# pandora_A_v1.net
KiCad netlist of a schematic drawn in EAGLE
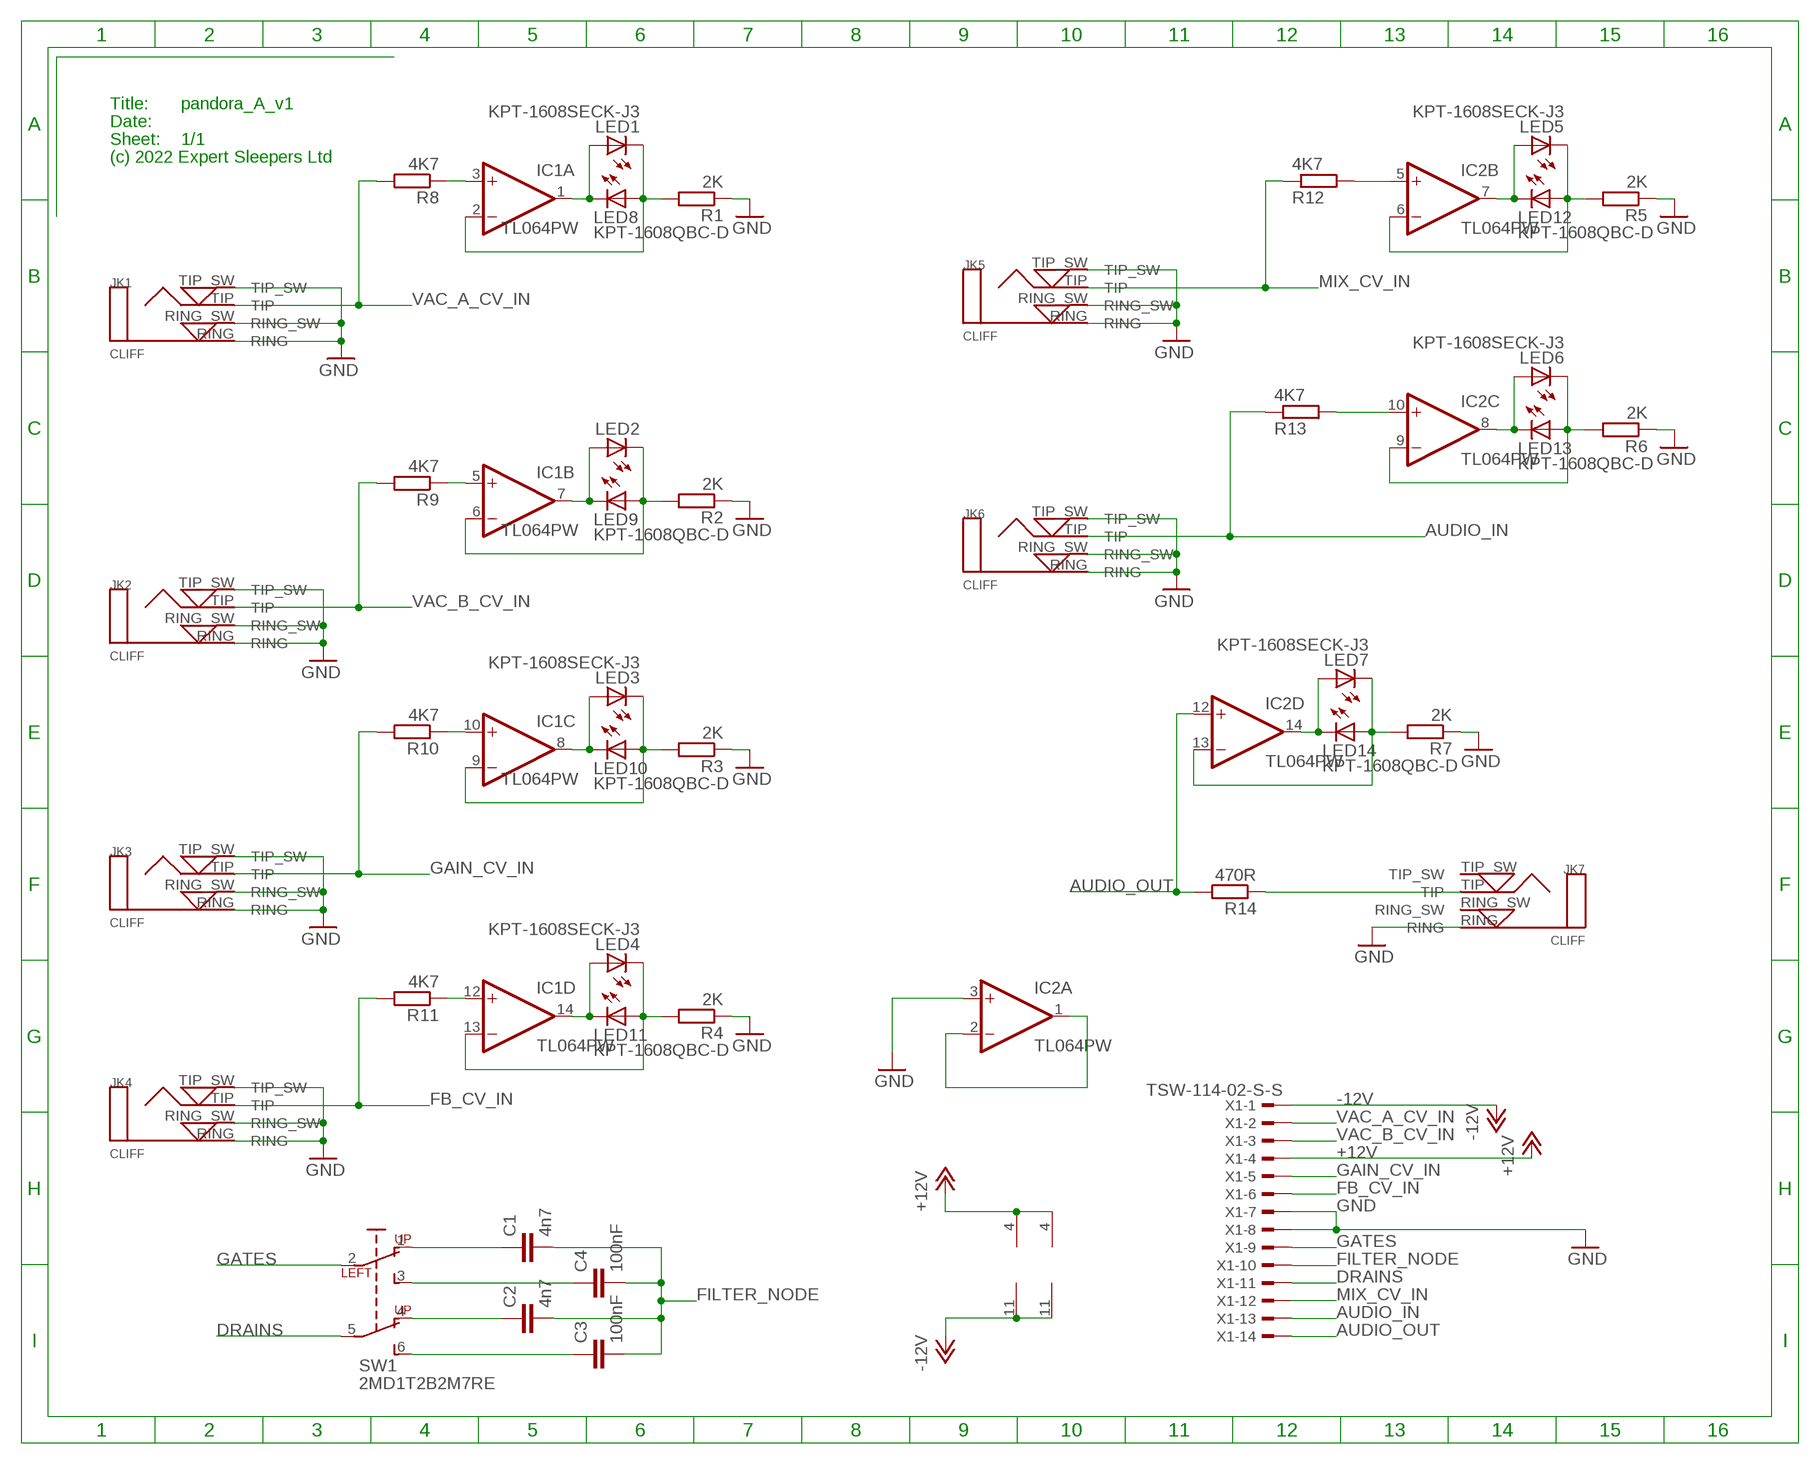
[diagram p0: schematic, sheet 1]

(export (version "E")
  (design (tool "Eeschema 10.0.6"))
  (components
    (comp (ref "C1")
      (value "4n7")
      (footprint "eagle-import:C0805")
      (libsource (lib "eagle-import") (part "C-EUC0805"))
    )
    (comp (ref "C2")
      (value "4n7")
      (footprint "eagle-import:C0805")
      (libsource (lib "eagle-import") (part "C-EUC0805"))
    )
    (comp (ref "C3")
      (value "100nF")
      (footprint "eagle-import:C1206")
      (libsource (lib "eagle-import") (part "C-EUC1206"))
    )
    (comp (ref "C4")
      (value "100nF")
      (footprint "eagle-import:C1206")
      (libsource (lib "eagle-import") (part "C-EUC1206"))
    )
    (comp (ref "IC1")
      (value "TL064PW")
      (footprint "eagle-import:PW_R-PDSO-G14")
      (libsource (lib "eagle-import") (part "TL074PW"))
    )
    (comp (ref "IC2")
      (value "TL064PW")
      (footprint "eagle-import:PW_R-PDSO-G14")
      (libsource (lib "eagle-import") (part "TL074PW"))
    )
    (comp (ref "JK1")
      (value "CLIFF")
      (footprint "eagle-import:CLIFF3.5MMPCB")
      (libsource (lib "eagle-import") (part "CLIFF3.5MM_PCB_SW_JK"))
    )
    (comp (ref "JK2")
      (value "CLIFF")
      (footprint "eagle-import:CLIFF3.5MMPCB")
      (libsource (lib "eagle-import") (part "CLIFF3.5MM_PCB_SW_JK"))
    )
    (comp (ref "JK3")
      (value "CLIFF")
      (footprint "eagle-import:CLIFF3.5MMPCB")
      (libsource (lib "eagle-import") (part "CLIFF3.5MM_PCB_SW_JK"))
    )
    (comp (ref "JK4")
      (value "CLIFF")
      (footprint "eagle-import:CLIFF3.5MMPCB")
      (libsource (lib "eagle-import") (part "CLIFF3.5MM_PCB_SW_JK"))
    )
    (comp (ref "JK5")
      (value "CLIFF")
      (footprint "eagle-import:CLIFF3.5MMPCB")
      (libsource (lib "eagle-import") (part "CLIFF3.5MM_PCB_SW_JK"))
    )
    (comp (ref "JK6")
      (value "CLIFF")
      (footprint "eagle-import:CLIFF3.5MMPCB")
      (libsource (lib "eagle-import") (part "CLIFF3.5MM_PCB_SW_JK"))
    )
    (comp (ref "JK7")
      (value "CLIFF")
      (footprint "eagle-import:CLIFF3.5MMPCB")
      (libsource (lib "eagle-import") (part "CLIFF3.5MM_PCB_SW_JK"))
    )
    (comp (ref "LED1")
      (value "KPT-1608SECK-J3")
      (footprint "eagle-import:CHIPLED_0603_LEFT")
      (libsource (lib "eagle-import") (part "KPT-1608SECK-J3"))
    )
    (comp (ref "LED2")
      (value "KPT-1608SECK-J3")
      (footprint "eagle-import:CHIPLED_0603_LEFT")
      (libsource (lib "eagle-import") (part "KPT-1608SECK-J3"))
    )
    (comp (ref "LED3")
      (value "KPT-1608SECK-J3")
      (footprint "eagle-import:CHIPLED_0603_LEFT")
      (libsource (lib "eagle-import") (part "KPT-1608SECK-J3"))
    )
    (comp (ref "LED4")
      (value "KPT-1608SECK-J3")
      (footprint "eagle-import:CHIPLED_0603_LEFT")
      (libsource (lib "eagle-import") (part "KPT-1608SECK-J3"))
    )
    (comp (ref "LED5")
      (value "KPT-1608SECK-J3")
      (footprint "eagle-import:CHIPLED_0603_LEFT")
      (libsource (lib "eagle-import") (part "KPT-1608SECK-J3"))
    )
    (comp (ref "LED6")
      (value "KPT-1608SECK-J3")
      (footprint "eagle-import:CHIPLED_0603_LEFT")
      (libsource (lib "eagle-import") (part "KPT-1608SECK-J3"))
    )
    (comp (ref "LED7")
      (value "KPT-1608SECK-J3")
      (footprint "eagle-import:CHIPLED_0603_LEFT")
      (libsource (lib "eagle-import") (part "KPT-1608SECK-J3"))
    )
    (comp (ref "LED8")
      (value "KPT-1608QBC-D")
      (footprint "eagle-import:CHIPLED_0603_RIGHT")
      (libsource (lib "eagle-import") (part "KPT-1608QBC-D"))
    )
    (comp (ref "LED9")
      (value "KPT-1608QBC-D")
      (footprint "eagle-import:CHIPLED_0603_RIGHT")
      (libsource (lib "eagle-import") (part "KPT-1608QBC-D"))
    )
    (comp (ref "LED10")
      (value "KPT-1608QBC-D")
      (footprint "eagle-import:CHIPLED_0603_RIGHT")
      (libsource (lib "eagle-import") (part "KPT-1608QBC-D"))
    )
    (comp (ref "LED11")
      (value "KPT-1608QBC-D")
      (footprint "eagle-import:CHIPLED_0603_RIGHT")
      (libsource (lib "eagle-import") (part "KPT-1608QBC-D"))
    )
    (comp (ref "LED12")
      (value "KPT-1608QBC-D")
      (footprint "eagle-import:CHIPLED_0603_RIGHT")
      (libsource (lib "eagle-import") (part "KPT-1608QBC-D"))
    )
    (comp (ref "LED13")
      (value "KPT-1608QBC-D")
      (footprint "eagle-import:CHIPLED_0603_RIGHT")
      (libsource (lib "eagle-import") (part "KPT-1608QBC-D"))
    )
    (comp (ref "LED14")
      (value "KPT-1608QBC-D")
      (footprint "eagle-import:CHIPLED_0603_RIGHT")
      (libsource (lib "eagle-import") (part "KPT-1608QBC-D"))
    )
    (comp (ref "R1")
      (value "2K")
      (footprint "eagle-import:R1206")
      (libsource (lib "eagle-import") (part "R-EU_R1206"))
    )
    (comp (ref "R2")
      (value "2K")
      (footprint "eagle-import:R1206")
      (libsource (lib "eagle-import") (part "R-EU_R1206"))
    )
    (comp (ref "R3")
      (value "2K")
      (footprint "eagle-import:R1206")
      (libsource (lib "eagle-import") (part "R-EU_R1206"))
    )
    (comp (ref "R4")
      (value "2K")
      (footprint "eagle-import:R1206")
      (libsource (lib "eagle-import") (part "R-EU_R1206"))
    )
    (comp (ref "R5")
      (value "2K")
      (footprint "eagle-import:R1206")
      (libsource (lib "eagle-import") (part "R-EU_R1206"))
    )
    (comp (ref "R6")
      (value "2K")
      (footprint "eagle-import:R1206")
      (libsource (lib "eagle-import") (part "R-EU_R1206"))
    )
    (comp (ref "R7")
      (value "2K")
      (footprint "eagle-import:R1206")
      (libsource (lib "eagle-import") (part "R-EU_R1206"))
    )
    (comp (ref "R8")
      (value "4K7")
      (footprint "eagle-import:R1206")
      (libsource (lib "eagle-import") (part "R-EU_R1206"))
    )
    (comp (ref "R9")
      (value "4K7")
      (footprint "eagle-import:R1206")
      (libsource (lib "eagle-import") (part "R-EU_R1206"))
    )
    (comp (ref "R10")
      (value "4K7")
      (footprint "eagle-import:R1206")
      (libsource (lib "eagle-import") (part "R-EU_R1206"))
    )
    (comp (ref "R11")
      (value "4K7")
      (footprint "eagle-import:R1206")
      (libsource (lib "eagle-import") (part "R-EU_R1206"))
    )
    (comp (ref "R12")
      (value "4K7")
      (footprint "eagle-import:R1206")
      (libsource (lib "eagle-import") (part "R-EU_R1206"))
    )
    (comp (ref "R13")
      (value "4K7")
      (footprint "eagle-import:R1206")
      (libsource (lib "eagle-import") (part "R-EU_R1206"))
    )
    (comp (ref "R14")
      (value "470R")
      (footprint "eagle-import:R1206")
      (libsource (lib "eagle-import") (part "R-EU_R1206"))
    )
    (comp (ref "SW1")
      (value "2MD1T2B2M7RE")
      (footprint "eagle-import:2MD1T2B2M7RE")
      (libsource (lib "eagle-import") (part "2MD1T2B2M7RE"))
    )
    (comp (ref "X1")
      (value "TSW-114-02-S-S")
      (footprint "eagle-import:TSW-114-02-S-S")
      (libsource (lib "eagle-import") (part "TSW-114-02-S-S"))
    )
  )
  (nets
    (net (code "1") (name "+12V") (class "Default")
      (node (ref "IC1") (pin "4") (pinfunction "V+_4") (pintype "power_in"))
      (node (ref "IC2") (pin "4") (pinfunction "V+_4") (pintype "power_in"))
      (node (ref "X1") (pin "4") (pinfunction "1_4") (pintype "passive"))
    )
    (net (code "2") (name "-12V") (class "Default")
      (node (ref "IC1") (pin "11") (pinfunction "V-_11") (pintype "power_in"))
      (node (ref "IC2") (pin "11") (pinfunction "V-_11") (pintype "power_in"))
      (node (ref "X1") (pin "1") (pinfunction "1_1") (pintype "passive"))
    )
    (net (code "3") (name "/AUDIO_IN") (class "Default")
      (node (ref "JK6") (pin "TIP") (pinfunction "TIP_TIP") (pintype "bidirectional"))
      (node (ref "R13") (pin "1") (pinfunction "1_1") (pintype "passive"))
      (node (ref "X1") (pin "13") (pinfunction "1_13") (pintype "passive"))
    )
    (net (code "4") (name "/AUDIO_OUT") (class "Default")
      (node (ref "IC2") (pin "12") (pinfunction "+IN_12") (pintype "input"))
      (node (ref "R14") (pin "2") (pinfunction "2_2") (pintype "passive"))
      (node (ref "X1") (pin "14") (pinfunction "1_14") (pintype "passive"))
    )
    (net (code "5") (name "/DRAINS") (class "Default")
      (node (ref "SW1") (pin "5") (pinfunction "PR_5") (pintype "passive"))
      (node (ref "X1") (pin "11") (pinfunction "1_11") (pintype "passive"))
    )
    (net (code "6") (name "/FB_CV_IN") (class "Default")
      (node (ref "JK4") (pin "TIP") (pinfunction "TIP_TIP") (pintype "bidirectional"))
      (node (ref "R11") (pin "2") (pinfunction "2_2") (pintype "passive"))
      (node (ref "X1") (pin "6") (pinfunction "1_6") (pintype "passive"))
    )
    (net (code "7") (name "/FILTER_NODE") (class "Default")
      (node (ref "C1") (pin "2") (pinfunction "2_2") (pintype "passive"))
      (node (ref "C2") (pin "2") (pinfunction "2_2") (pintype "passive"))
      (node (ref "C3") (pin "2") (pinfunction "2_2") (pintype "passive"))
      (node (ref "C4") (pin "2") (pinfunction "2_2") (pintype "passive"))
      (node (ref "X1") (pin "10") (pinfunction "1_10") (pintype "passive"))
    )
    (net (code "8") (name "/GAIN_CV_IN") (class "Default")
      (node (ref "JK3") (pin "TIP") (pinfunction "TIP_TIP") (pintype "bidirectional"))
      (node (ref "R10") (pin "2") (pinfunction "2_2") (pintype "passive"))
      (node (ref "X1") (pin "5") (pinfunction "1_5") (pintype "passive"))
    )
    (net (code "9") (name "/GATES") (class "Default")
      (node (ref "SW1") (pin "2") (pinfunction "PL_2") (pintype "passive"))
      (node (ref "X1") (pin "9") (pinfunction "1_9") (pintype "passive"))
    )
    (net (code "10") (name "/MIX_CV_IN") (class "Default")
      (node (ref "JK5") (pin "TIP") (pinfunction "TIP_TIP") (pintype "bidirectional"))
      (node (ref "R12") (pin "1") (pinfunction "1_1") (pintype "passive"))
      (node (ref "X1") (pin "12") (pinfunction "1_12") (pintype "passive"))
    )
    (net (code "11") (name "/VAC_A_CV_IN") (class "Default")
      (node (ref "JK1") (pin "TIP") (pinfunction "TIP_TIP") (pintype "bidirectional"))
      (node (ref "R8") (pin "2") (pinfunction "2_2") (pintype "passive"))
      (node (ref "X1") (pin "2") (pinfunction "1_2") (pintype "passive"))
    )
    (net (code "12") (name "/VAC_B_CV_IN") (class "Default")
      (node (ref "JK2") (pin "TIP") (pinfunction "TIP_TIP") (pintype "bidirectional"))
      (node (ref "R9") (pin "2") (pinfunction "2_2") (pintype "passive"))
      (node (ref "X1") (pin "3") (pinfunction "1_3") (pintype "passive"))
    )
    (net (code "13") (name "GND") (class "Default")
      (node (ref "IC2") (pin "3") (pinfunction "+IN_3") (pintype "input"))
      (node (ref "JK1") (pin "RING") (pinfunction "RING_RING") (pintype "bidirectional"))
      (node (ref "JK1") (pin "RING_SW") (pinfunction "RING_SW_RING_SW") (pintype "bidirectional"))
      (node (ref "JK1") (pin "TIP_SW") (pinfunction "TIP_SW_TIP_SW") (pintype "bidirectional"))
      (node (ref "JK2") (pin "RING") (pinfunction "RING_RING") (pintype "bidirectional"))
      (node (ref "JK2") (pin "RING_SW") (pinfunction "RING_SW_RING_SW") (pintype "bidirectional"))
      (node (ref "JK2") (pin "TIP_SW") (pinfunction "TIP_SW_TIP_SW") (pintype "bidirectional"))
      (node (ref "JK3") (pin "RING") (pinfunction "RING_RING") (pintype "bidirectional"))
      (node (ref "JK3") (pin "RING_SW") (pinfunction "RING_SW_RING_SW") (pintype "bidirectional"))
      (node (ref "JK3") (pin "TIP_SW") (pinfunction "TIP_SW_TIP_SW") (pintype "bidirectional"))
      (node (ref "JK4") (pin "RING") (pinfunction "RING_RING") (pintype "bidirectional"))
      (node (ref "JK4") (pin "RING_SW") (pinfunction "RING_SW_RING_SW") (pintype "bidirectional"))
      (node (ref "JK4") (pin "TIP_SW") (pinfunction "TIP_SW_TIP_SW") (pintype "bidirectional"))
      (node (ref "JK5") (pin "RING") (pinfunction "RING_RING") (pintype "bidirectional"))
      (node (ref "JK5") (pin "RING_SW") (pinfunction "RING_SW_RING_SW") (pintype "bidirectional"))
      (node (ref "JK5") (pin "TIP_SW") (pinfunction "TIP_SW_TIP_SW") (pintype "bidirectional"))
      (node (ref "JK6") (pin "RING") (pinfunction "RING_RING") (pintype "bidirectional"))
      (node (ref "JK6") (pin "RING_SW") (pinfunction "RING_SW_RING_SW") (pintype "bidirectional"))
      (node (ref "JK6") (pin "TIP_SW") (pinfunction "TIP_SW_TIP_SW") (pintype "bidirectional"))
      (node (ref "JK7") (pin "RING") (pinfunction "RING_RING") (pintype "bidirectional"))
      (node (ref "R1") (pin "1") (pinfunction "1_1") (pintype "passive"))
      (node (ref "R2") (pin "1") (pinfunction "1_1") (pintype "passive"))
      (node (ref "R3") (pin "1") (pinfunction "1_1") (pintype "passive"))
      (node (ref "R4") (pin "1") (pinfunction "1_1") (pintype "passive"))
      (node (ref "R5") (pin "1") (pinfunction "1_1") (pintype "passive"))
      (node (ref "R6") (pin "1") (pinfunction "1_1") (pintype "passive"))
      (node (ref "R7") (pin "1") (pinfunction "1_1") (pintype "passive"))
      (node (ref "X1") (pin "7") (pinfunction "1_7") (pintype "passive"))
      (node (ref "X1") (pin "8") (pinfunction "1_8") (pintype "passive"))
    )
    (net (code "14") (name "Net-(IC1A-+IN)") (class "Default")
      (node (ref "IC1") (pin "3") (pinfunction "+IN_3") (pintype "input"))
      (node (ref "R8") (pin "1") (pinfunction "1_1") (pintype "passive"))
    )
    (net (code "15") (name "Net-(IC1A--IN)") (class "Default")
      (node (ref "IC1") (pin "2") (pinfunction "-IN_2") (pintype "input"))
      (node (ref "LED1") (pin "1") (pinfunction "C_1") (pintype "passive"))
      (node (ref "LED8") (pin "1") (pinfunction "A_1") (pintype "passive"))
      (node (ref "R1") (pin "2") (pinfunction "2_2") (pintype "passive"))
    )
    (net (code "16") (name "Net-(IC1A-OUT)") (class "Default")
      (node (ref "IC1") (pin "1") (pinfunction "OUT_1") (pintype "output"))
      (node (ref "LED1") (pin "2") (pinfunction "A_2") (pintype "passive"))
      (node (ref "LED8") (pin "2") (pinfunction "C_2") (pintype "passive"))
    )
    (net (code "17") (name "Net-(IC1B-+IN)") (class "Default")
      (node (ref "IC1") (pin "5") (pinfunction "+IN_5") (pintype "input"))
      (node (ref "R9") (pin "1") (pinfunction "1_1") (pintype "passive"))
    )
    (net (code "18") (name "Net-(IC1B--IN)") (class "Default")
      (node (ref "IC1") (pin "6") (pinfunction "-IN_6") (pintype "input"))
      (node (ref "LED2") (pin "1") (pinfunction "C_1") (pintype "passive"))
      (node (ref "LED9") (pin "1") (pinfunction "A_1") (pintype "passive"))
      (node (ref "R2") (pin "2") (pinfunction "2_2") (pintype "passive"))
    )
    (net (code "19") (name "Net-(IC1B-OUT)") (class "Default")
      (node (ref "IC1") (pin "7") (pinfunction "OUT_7") (pintype "output"))
      (node (ref "LED2") (pin "2") (pinfunction "A_2") (pintype "passive"))
      (node (ref "LED9") (pin "2") (pinfunction "C_2") (pintype "passive"))
    )
    (net (code "20") (name "Net-(IC1C-+IN)") (class "Default")
      (node (ref "IC1") (pin "10") (pinfunction "+IN_10") (pintype "input"))
      (node (ref "R10") (pin "1") (pinfunction "1_1") (pintype "passive"))
    )
    (net (code "21") (name "Net-(IC1C--IN)") (class "Default")
      (node (ref "IC1") (pin "9") (pinfunction "-IN_9") (pintype "input"))
      (node (ref "LED10") (pin "1") (pinfunction "A_1") (pintype "passive"))
      (node (ref "LED3") (pin "1") (pinfunction "C_1") (pintype "passive"))
      (node (ref "R3") (pin "2") (pinfunction "2_2") (pintype "passive"))
    )
    (net (code "22") (name "Net-(IC1C-OUT)") (class "Default")
      (node (ref "IC1") (pin "8") (pinfunction "OUT_8") (pintype "output"))
      (node (ref "LED10") (pin "2") (pinfunction "C_2") (pintype "passive"))
      (node (ref "LED3") (pin "2") (pinfunction "A_2") (pintype "passive"))
    )
    (net (code "23") (name "Net-(IC1D-+IN)") (class "Default")
      (node (ref "IC1") (pin "12") (pinfunction "+IN_12") (pintype "input"))
      (node (ref "R11") (pin "1") (pinfunction "1_1") (pintype "passive"))
    )
    (net (code "24") (name "Net-(IC1D--IN)") (class "Default")
      (node (ref "IC1") (pin "13") (pinfunction "-IN_13") (pintype "input"))
      (node (ref "LED11") (pin "1") (pinfunction "A_1") (pintype "passive"))
      (node (ref "LED4") (pin "1") (pinfunction "C_1") (pintype "passive"))
      (node (ref "R4") (pin "2") (pinfunction "2_2") (pintype "passive"))
    )
    (net (code "25") (name "Net-(IC1D-OUT)") (class "Default")
      (node (ref "IC1") (pin "14") (pinfunction "OUT_14") (pintype "output"))
      (node (ref "LED11") (pin "2") (pinfunction "C_2") (pintype "passive"))
      (node (ref "LED4") (pin "2") (pinfunction "A_2") (pintype "passive"))
    )
    (net (code "26") (name "Net-(IC2A--IN)") (class "Default")
      (node (ref "IC2") (pin "1") (pinfunction "OUT_1") (pintype "output"))
      (node (ref "IC2") (pin "2") (pinfunction "-IN_2") (pintype "input"))
    )
    (net (code "27") (name "Net-(IC2B-+IN)") (class "Default")
      (node (ref "IC2") (pin "5") (pinfunction "+IN_5") (pintype "input"))
      (node (ref "R12") (pin "2") (pinfunction "2_2") (pintype "passive"))
    )
    (net (code "28") (name "Net-(IC2B--IN)") (class "Default")
      (node (ref "IC2") (pin "6") (pinfunction "-IN_6") (pintype "input"))
      (node (ref "LED12") (pin "1") (pinfunction "A_1") (pintype "passive"))
      (node (ref "LED5") (pin "1") (pinfunction "C_1") (pintype "passive"))
      (node (ref "R5") (pin "2") (pinfunction "2_2") (pintype "passive"))
    )
    (net (code "29") (name "Net-(IC2B-OUT)") (class "Default")
      (node (ref "IC2") (pin "7") (pinfunction "OUT_7") (pintype "output"))
      (node (ref "LED12") (pin "2") (pinfunction "C_2") (pintype "passive"))
      (node (ref "LED5") (pin "2") (pinfunction "A_2") (pintype "passive"))
    )
    (net (code "30") (name "Net-(IC2C-+IN)") (class "Default")
      (node (ref "IC2") (pin "10") (pinfunction "+IN_10") (pintype "input"))
      (node (ref "R13") (pin "2") (pinfunction "2_2") (pintype "passive"))
    )
    (net (code "31") (name "Net-(IC2C--IN)") (class "Default")
      (node (ref "IC2") (pin "9") (pinfunction "-IN_9") (pintype "input"))
      (node (ref "LED13") (pin "1") (pinfunction "A_1") (pintype "passive"))
      (node (ref "LED6") (pin "1") (pinfunction "C_1") (pintype "passive"))
      (node (ref "R6") (pin "2") (pinfunction "2_2") (pintype "passive"))
    )
    (net (code "32") (name "Net-(IC2C-OUT)") (class "Default")
      (node (ref "IC2") (pin "8") (pinfunction "OUT_8") (pintype "output"))
      (node (ref "LED13") (pin "2") (pinfunction "C_2") (pintype "passive"))
      (node (ref "LED6") (pin "2") (pinfunction "A_2") (pintype "passive"))
    )
    (net (code "33") (name "Net-(IC2D--IN)") (class "Default")
      (node (ref "IC2") (pin "13") (pinfunction "-IN_13") (pintype "input"))
      (node (ref "LED14") (pin "1") (pinfunction "A_1") (pintype "passive"))
      (node (ref "LED7") (pin "1") (pinfunction "C_1") (pintype "passive"))
      (node (ref "R7") (pin "2") (pinfunction "2_2") (pintype "passive"))
    )
    (net (code "34") (name "Net-(IC2D-OUT)") (class "Default")
      (node (ref "IC2") (pin "14") (pinfunction "OUT_14") (pintype "output"))
      (node (ref "LED14") (pin "2") (pinfunction "C_2") (pintype "passive"))
      (node (ref "LED7") (pin "2") (pinfunction "A_2") (pintype "passive"))
    )
    (net (code "35") (name "Net-(JK7-PadTIP)") (class "Default")
      (node (ref "JK7") (pin "TIP") (pinfunction "TIP_TIP") (pintype "bidirectional"))
      (node (ref "R14") (pin "1") (pinfunction "1_1") (pintype "passive"))
    )
    (net (code "36") (name "Net-(SW1-LD)") (class "Default")
      (node (ref "C4") (pin "1") (pinfunction "1_1") (pintype "passive"))
      (node (ref "SW1") (pin "3") (pinfunction "LD_3") (pintype "passive"))
    )
    (net (code "37") (name "Net-(SW1-LU)") (class "Default")
      (node (ref "C1") (pin "1") (pinfunction "1_1") (pintype "passive"))
      (node (ref "SW1") (pin "1") (pinfunction "LU_1") (pintype "passive"))
    )
    (net (code "38") (name "Net-(SW1-RD)") (class "Default")
      (node (ref "C3") (pin "1") (pinfunction "1_1") (pintype "passive"))
      (node (ref "SW1") (pin "6") (pinfunction "RD_6") (pintype "passive"))
    )
    (net (code "39") (name "Net-(SW1-RU)") (class "Default")
      (node (ref "C2") (pin "1") (pinfunction "1_1") (pintype "passive"))
      (node (ref "SW1") (pin "4") (pinfunction "RU_4") (pintype "passive"))
    )
    (net (code "40") (name "unconnected-(JK7-PadRING_SW)") (class "Default")
      (node (ref "JK7") (pin "RING_SW") (pinfunction "RING_SW_RING_SW") (pintype "bidirectional"))
    )
    (net (code "41") (name "unconnected-(JK7-PadTIP_SW)") (class "Default")
      (node (ref "JK7") (pin "TIP_SW") (pinfunction "TIP_SW_TIP_SW") (pintype "bidirectional"))
    )
  )
)
